# oscillateur.net
KiCad netlist of a schematic drawn in EAGLE
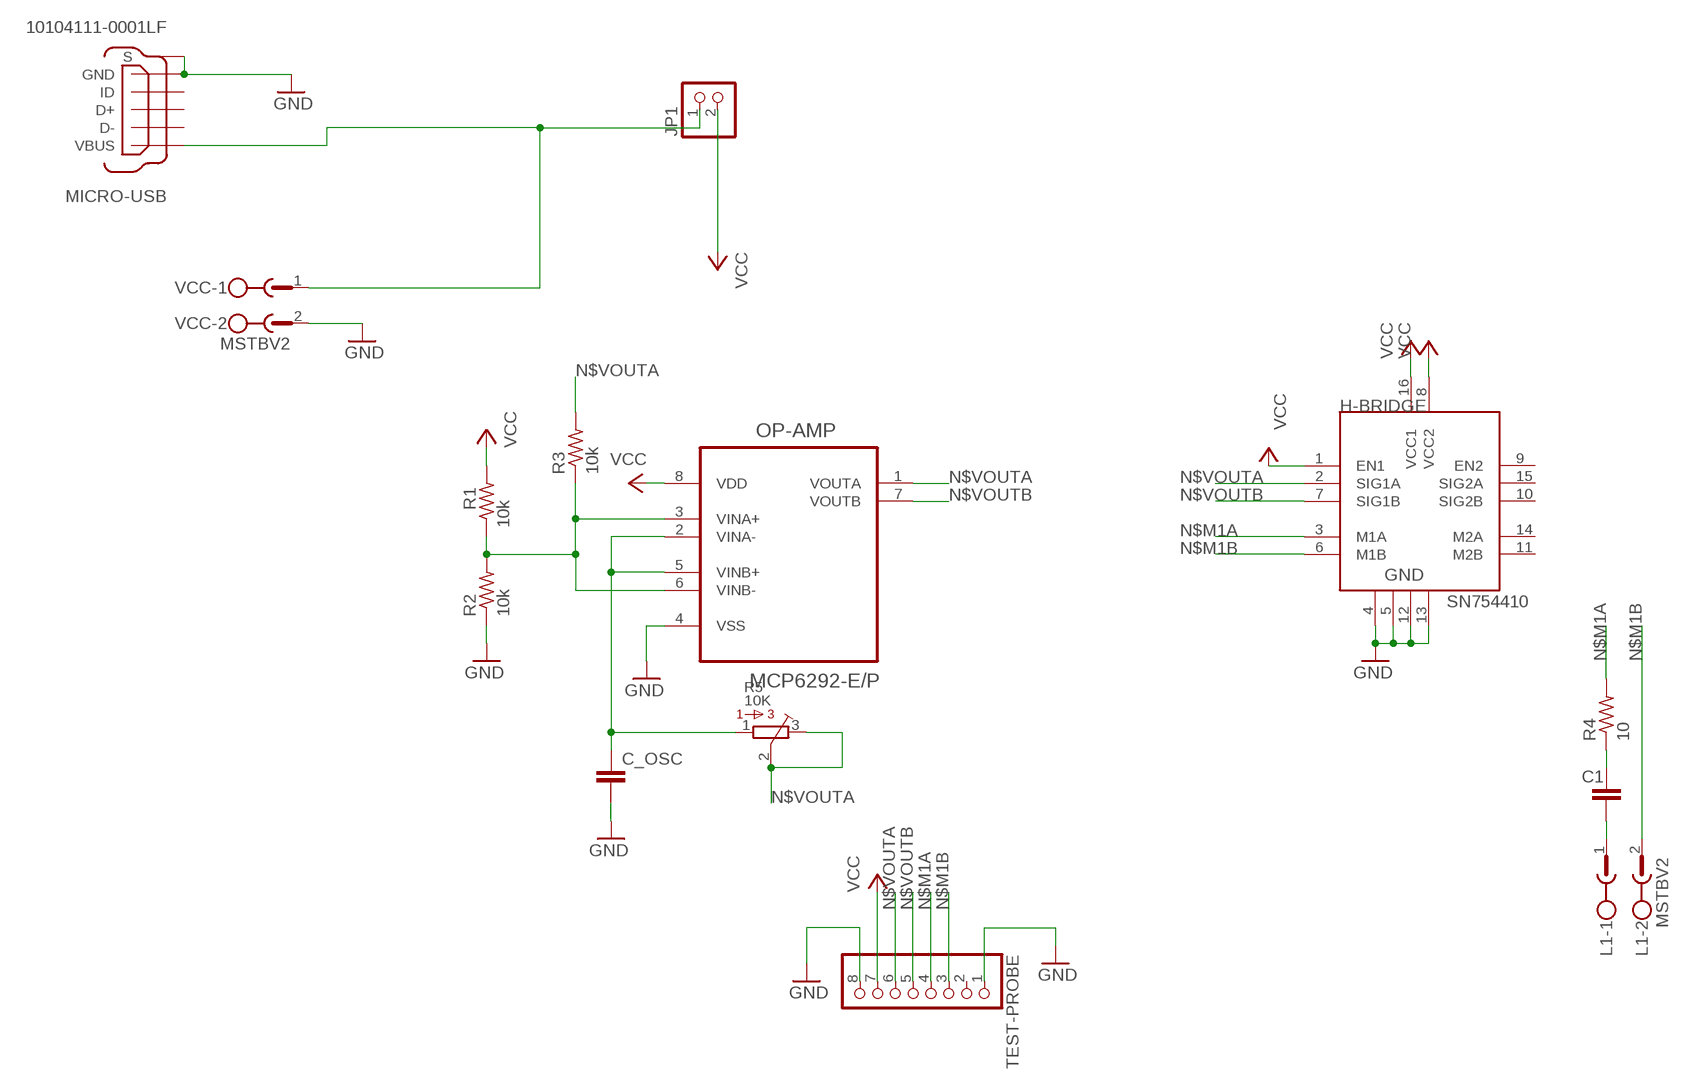
[diagram p0: schematic, sheet 1]

(export (version "E")
  (design (tool "Eeschema 10.0.6"))
  (components
    (comp (ref "C1")
      (value "C5/2.5")
      (footprint "eagle-import:C5B2.5")
      (libsource (lib "eagle-import") (part "C5/2.5"))
    )
    (comp (ref "C_OSC")
      (value "C5/2.5")
      (footprint "eagle-import:C5B2.5")
      (libsource (lib "eagle-import") (part "C5/2.5"))
    )
    (comp (ref "H-BRIDGE")
      (value "SN754410")
      (footprint "eagle-import:DIP16")
      (libsource (lib "eagle-import") (part "SN754410"))
    )
    (comp (ref "JP1")
      (value "PINHD-1X2")
      (footprint "eagle-import:1X02")
      (libsource (lib "eagle-import") (part "PINHD-1X2"))
    )
    (comp (ref "L1")
      (value "MSTBV2")
      (footprint "eagle-import:MSTBV2")
      (fields (field (name "MPN") "MSTBV 2,5/2-GF-5.08"))
      (libsource (lib "eagle-import") (part "MSTBV2"))
    )
    (comp (ref "MICRO-USB")
      (value "10104111-0001LF")
      (footprint "eagle-import:FRAMATOME_10104111-0001LF")
      (fields (field (name "MF") "Amphenol ICC"))
      (libsource (lib "eagle-import") (part "10104111-0001LF"))
    )
    (comp (ref "OP-AMP")
      (value "MCP6292-E/P")
      (footprint "eagle-import:DIP254P762X432-8")
      (fields (field (name "MF") "Microchip"))
      (libsource (lib "eagle-import") (part "MCP6292-E/P"))
    )
    (comp (ref "R1")
      (value "10k")
      (footprint "eagle-import:0207_10")
      (libsource (lib "eagle-import") (part "R-US_0207/10"))
    )
    (comp (ref "R2")
      (value "10k")
      (footprint "eagle-import:0207_10")
      (libsource (lib "eagle-import") (part "R-US_0207/10"))
    )
    (comp (ref "R3")
      (value "10k")
      (footprint "eagle-import:0207_10")
      (libsource (lib "eagle-import") (part "R-US_0207/10"))
    )
    (comp (ref "R4")
      (value "10")
      (footprint "eagle-import:0207_10")
      (libsource (lib "eagle-import") (part "R-US_0207/10"))
    )
    (comp (ref "R5")
      (value "10K")
      (footprint "eagle-import:3362R")
      (libsource (lib "eagle-import") (part "3362R"))
    )
    (comp (ref "TEST-PROBE")
      (value "PINHD-1X8")
      (footprint "eagle-import:1X08")
      (libsource (lib "eagle-import") (part "PINHD-1X8"))
    )
    (comp (ref "VCC")
      (value "MSTBV2")
      (footprint "eagle-import:MSTBV2")
      (fields (field (name "MPN") "MSTBV 2,5/2-GF-5.08"))
      (libsource (lib "eagle-import") (part "MSTBV2"))
    )
  )
  (nets
    (net (code "1") (name "/N$M1A") (class "Default")
      (node (ref "H-BRIDGE") (pin "3") (pinfunction "M1A_3") (pintype "bidirectional"))
      (node (ref "R4") (pin "2") (pinfunction "2_2") (pintype "passive"))
      (node (ref "TEST-PROBE") (pin "4") (pinfunction "4_4") (pintype "passive"))
    )
    (net (code "2") (name "/N$M1B") (class "Default")
      (node (ref "H-BRIDGE") (pin "6") (pinfunction "M1B_6") (pintype "bidirectional"))
      (node (ref "L1") (pin "2") (pinfunction "1_2") (pintype "passive"))
      (node (ref "TEST-PROBE") (pin "3") (pinfunction "3_3") (pintype "passive"))
    )
    (net (code "3") (name "/N$VOUTA") (class "Default")
      (node (ref "H-BRIDGE") (pin "2") (pinfunction "SIG1A_2") (pintype "bidirectional"))
      (node (ref "OP-AMP") (pin "1") (pinfunction "VOUTA_1") (pintype "output"))
      (node (ref "R3") (pin "2") (pinfunction "2_2") (pintype "passive"))
      (node (ref "R5") (pin "2") (pinfunction "2_2") (pintype "passive"))
      (node (ref "R5") (pin "3") (pinfunction "3_3") (pintype "passive"))
      (node (ref "TEST-PROBE") (pin "6") (pinfunction "6_6") (pintype "passive"))
    )
    (net (code "4") (name "/N$VOUTB") (class "Default")
      (node (ref "H-BRIDGE") (pin "7") (pinfunction "SIG1B_7") (pintype "bidirectional"))
      (node (ref "OP-AMP") (pin "7") (pinfunction "VOUTB_7") (pintype "output"))
      (node (ref "TEST-PROBE") (pin "5") (pinfunction "5_5") (pintype "passive"))
    )
    (net (code "5") (name "GND") (class "Default")
      (node (ref "C_OSC") (pin "2") (pinfunction "2_2") (pintype "passive"))
      (node (ref "H-BRIDGE") (pin "12") (pinfunction "P12_12") (pintype "power_in"))
      (node (ref "H-BRIDGE") (pin "13") (pinfunction "P13_13") (pintype "power_in"))
      (node (ref "H-BRIDGE") (pin "4") (pinfunction "P4_4") (pintype "power_in"))
      (node (ref "H-BRIDGE") (pin "5") (pinfunction "P5_5") (pintype "power_in"))
      (node (ref "MICRO-USB") (pin "5") (pinfunction "GND_5") (pintype "power_in"))
      (node (ref "MICRO-USB") (pin "6") (pinfunction "S_6") (pintype "power_in"))
      (node (ref "MICRO-USB") (pin "7") (pinfunction "S_7") (pintype "power_in"))
      (node (ref "MICRO-USB") (pin "8") (pinfunction "S_8") (pintype "power_in"))
      (node (ref "MICRO-USB") (pin "9") (pinfunction "S_9") (pintype "power_in"))
      (node (ref "OP-AMP") (pin "4") (pinfunction "VSS_4") (pintype "power_in"))
      (node (ref "R2") (pin "1") (pinfunction "1_1") (pintype "passive"))
      (node (ref "TEST-PROBE") (pin "1") (pinfunction "1_1") (pintype "passive"))
      (node (ref "TEST-PROBE") (pin "8") (pinfunction "8_8") (pintype "passive"))
      (node (ref "VCC") (pin "2") (pinfunction "1_2") (pintype "passive"))
    )
    (net (code "6") (name "Net-(C1-Pad1)") (class "Default")
      (node (ref "C1") (pin "1") (pinfunction "1_1") (pintype "passive"))
      (node (ref "R4") (pin "1") (pinfunction "1_1") (pintype "passive"))
    )
    (net (code "7") (name "Net-(C1-Pad2)") (class "Default")
      (node (ref "C1") (pin "2") (pinfunction "2_2") (pintype "passive"))
      (node (ref "L1") (pin "1") (pinfunction "1_1") (pintype "passive"))
    )
    (net (code "8") (name "Net-(MICRO-USB-VBUS)") (class "Default")
      (node (ref "JP1") (pin "1") (pinfunction "1_1") (pintype "passive"))
      (node (ref "MICRO-USB") (pin "1") (pinfunction "VBUS_1") (pintype "power_in"))
      (node (ref "VCC") (pin "1") (pinfunction "1_1") (pintype "passive"))
    )
    (net (code "9") (name "Net-(OP-AMP-VINA+)") (class "Default")
      (node (ref "OP-AMP") (pin "3") (pinfunction "VINA+_3") (pintype "input"))
      (node (ref "OP-AMP") (pin "6") (pinfunction "VINB-_6") (pintype "input"))
      (node (ref "R1") (pin "1") (pinfunction "1_1") (pintype "passive"))
      (node (ref "R2") (pin "2") (pinfunction "2_2") (pintype "passive"))
      (node (ref "R3") (pin "1") (pinfunction "1_1") (pintype "passive"))
    )
    (net (code "10") (name "Net-(OP-AMP-VINA-)") (class "Default")
      (node (ref "C_OSC") (pin "1") (pinfunction "1_1") (pintype "passive"))
      (node (ref "OP-AMP") (pin "2") (pinfunction "VINA-_2") (pintype "input"))
      (node (ref "OP-AMP") (pin "5") (pinfunction "VINB+_5") (pintype "input"))
      (node (ref "R5") (pin "1") (pinfunction "1_1") (pintype "passive"))
    )
    (net (code "11") (name "VCC") (class "Default")
      (node (ref "H-BRIDGE") (pin "1") (pinfunction "EN1_1") (pintype "bidirectional"))
      (node (ref "H-BRIDGE") (pin "16") (pinfunction "VCC1_16") (pintype "power_in"))
      (node (ref "H-BRIDGE") (pin "8") (pinfunction "VCC2_8") (pintype "power_in"))
      (node (ref "JP1") (pin "2") (pinfunction "2_2") (pintype "passive"))
      (node (ref "OP-AMP") (pin "8") (pinfunction "VDD_8") (pintype "power_in"))
      (node (ref "R1") (pin "2") (pinfunction "2_2") (pintype "passive"))
      (node (ref "TEST-PROBE") (pin "7") (pinfunction "7_7") (pintype "passive"))
    )
    (net (code "12") (name "unconnected-(H-BRIDGE-EN2-Pad9)") (class "Default")
      (node (ref "H-BRIDGE") (pin "9") (pinfunction "EN2_9") (pintype "bidirectional"))
    )
    (net (code "13") (name "unconnected-(H-BRIDGE-M2A-Pad14)") (class "Default")
      (node (ref "H-BRIDGE") (pin "14") (pinfunction "M2A_14") (pintype "bidirectional"))
    )
    (net (code "14") (name "unconnected-(H-BRIDGE-M2B-Pad11)") (class "Default")
      (node (ref "H-BRIDGE") (pin "11") (pinfunction "M2B_11") (pintype "bidirectional"))
    )
    (net (code "15") (name "unconnected-(H-BRIDGE-SIG2A-Pad15)") (class "Default")
      (node (ref "H-BRIDGE") (pin "15") (pinfunction "SIG2A_15") (pintype "bidirectional"))
    )
    (net (code "16") (name "unconnected-(H-BRIDGE-SIG2B-Pad10)") (class "Default")
      (node (ref "H-BRIDGE") (pin "10") (pinfunction "SIG2B_10") (pintype "bidirectional"))
    )
    (net (code "17") (name "unconnected-(MICRO-USB-D+-Pad3)") (class "Default")
      (node (ref "MICRO-USB") (pin "3") (pinfunction "D+_3") (pintype "passive"))
    )
    (net (code "18") (name "unconnected-(MICRO-USB-D--Pad2)") (class "Default")
      (node (ref "MICRO-USB") (pin "2") (pinfunction "D-_2") (pintype "passive"))
    )
    (net (code "19") (name "unconnected-(MICRO-USB-ID-Pad4)") (class "Default")
      (node (ref "MICRO-USB") (pin "4") (pinfunction "ID_4") (pintype "passive"))
    )
    (net (code "20") (name "unconnected-(TEST-PROBE-Pad2)") (class "Default")
      (node (ref "TEST-PROBE") (pin "2") (pinfunction "2_2") (pintype "passive"))
    )
  )
)
